# currentsensor.net
KiCad netlist of a schematic drawn in EAGLE
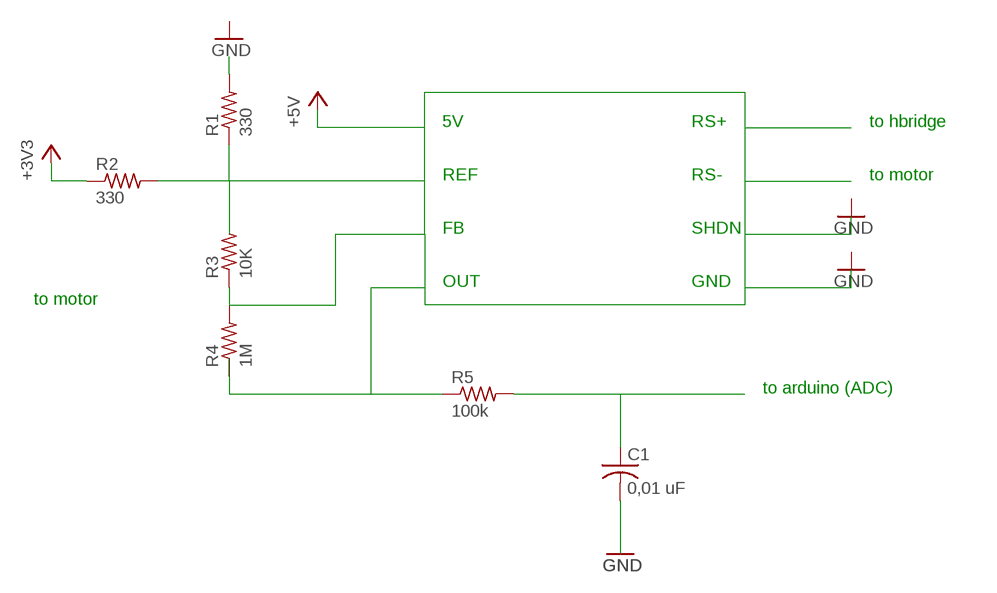
[diagram p0: schematic, sheet 1]

(export (version "E")
  (design (tool "Eeschema 10.0.6"))
  (components
    (comp (ref "C1")
      (value "0,01 uF")
      (footprint "eagle-import:C025-030X050")
      (libsource (lib "eagle-import") (part "C-US025-030X050"))
    )
    (comp (ref "R1")
      (value "330")
      (footprint "eagle-import:0207_5V")
      (libsource (lib "eagle-import") (part "R-US_0207/5V"))
    )
    (comp (ref "R2")
      (value "330")
      (footprint "eagle-import:0207_5V")
      (libsource (lib "eagle-import") (part "R-US_0207/5V"))
    )
    (comp (ref "R3")
      (value "10K")
      (footprint "eagle-import:0207_5V")
      (libsource (lib "eagle-import") (part "R-US_0207/5V"))
    )
    (comp (ref "R4")
      (value "1M")
      (footprint "eagle-import:0207_5V")
      (libsource (lib "eagle-import") (part "R-US_0207/5V"))
    )
    (comp (ref "R5")
      (value "100k")
      (footprint "eagle-import:0207_5V")
      (libsource (lib "eagle-import") (part "R-US_0207/5V"))
    )
  )
  (nets
    (net (code "1") (name "+3V3") (class "Default")
      (node (ref "R2") (pin "1") (pinfunction "1_1") (pintype "passive"))
    )
    (net (code "2") (name "+5V") (class "Default")
      (node (ref "R1") (pin "1") (pinfunction "1_1") (pintype "passive"))
      (node (ref "R2") (pin "2") (pinfunction "2_2") (pintype "passive"))
      (node (ref "R3") (pin "1") (pinfunction "1_1") (pintype "passive"))
      (node (ref "R4") (pin "2") (pinfunction "2_2") (pintype "passive"))
      (node (ref "R5") (pin "1") (pinfunction "1_1") (pintype "passive"))
    )
    (net (code "4") (name "Net-(C1-Pad1)") (class "Default")
      (node (ref "C1") (pin "1") (pinfunction "1_1") (pintype "passive"))
      (node (ref "R5") (pin "2") (pinfunction "2_2") (pintype "passive"))
    )
    (net (code "5") (name "unconnected-(C1-Pad2)") (class "Default")
      (node (ref "C1") (pin "2") (pinfunction "2_2") (pintype "passive"))
    )
    (net (code "6") (name "unconnected-(R1-Pad2)") (class "Default")
      (node (ref "R1") (pin "2") (pinfunction "2_2") (pintype "passive"))
    )
    (net (code "7") (name "unconnected-(R3-Pad2)") (class "Default")
      (node (ref "R3") (pin "2") (pinfunction "2_2") (pintype "passive"))
    )
    (net (code "8") (name "unconnected-(R4-Pad1)") (class "Default")
      (node (ref "R4") (pin "1") (pinfunction "1_1") (pintype "passive"))
    )
  )
)
